# 12VPart.net
KiCad netlist of a schematic drawn in EAGLE
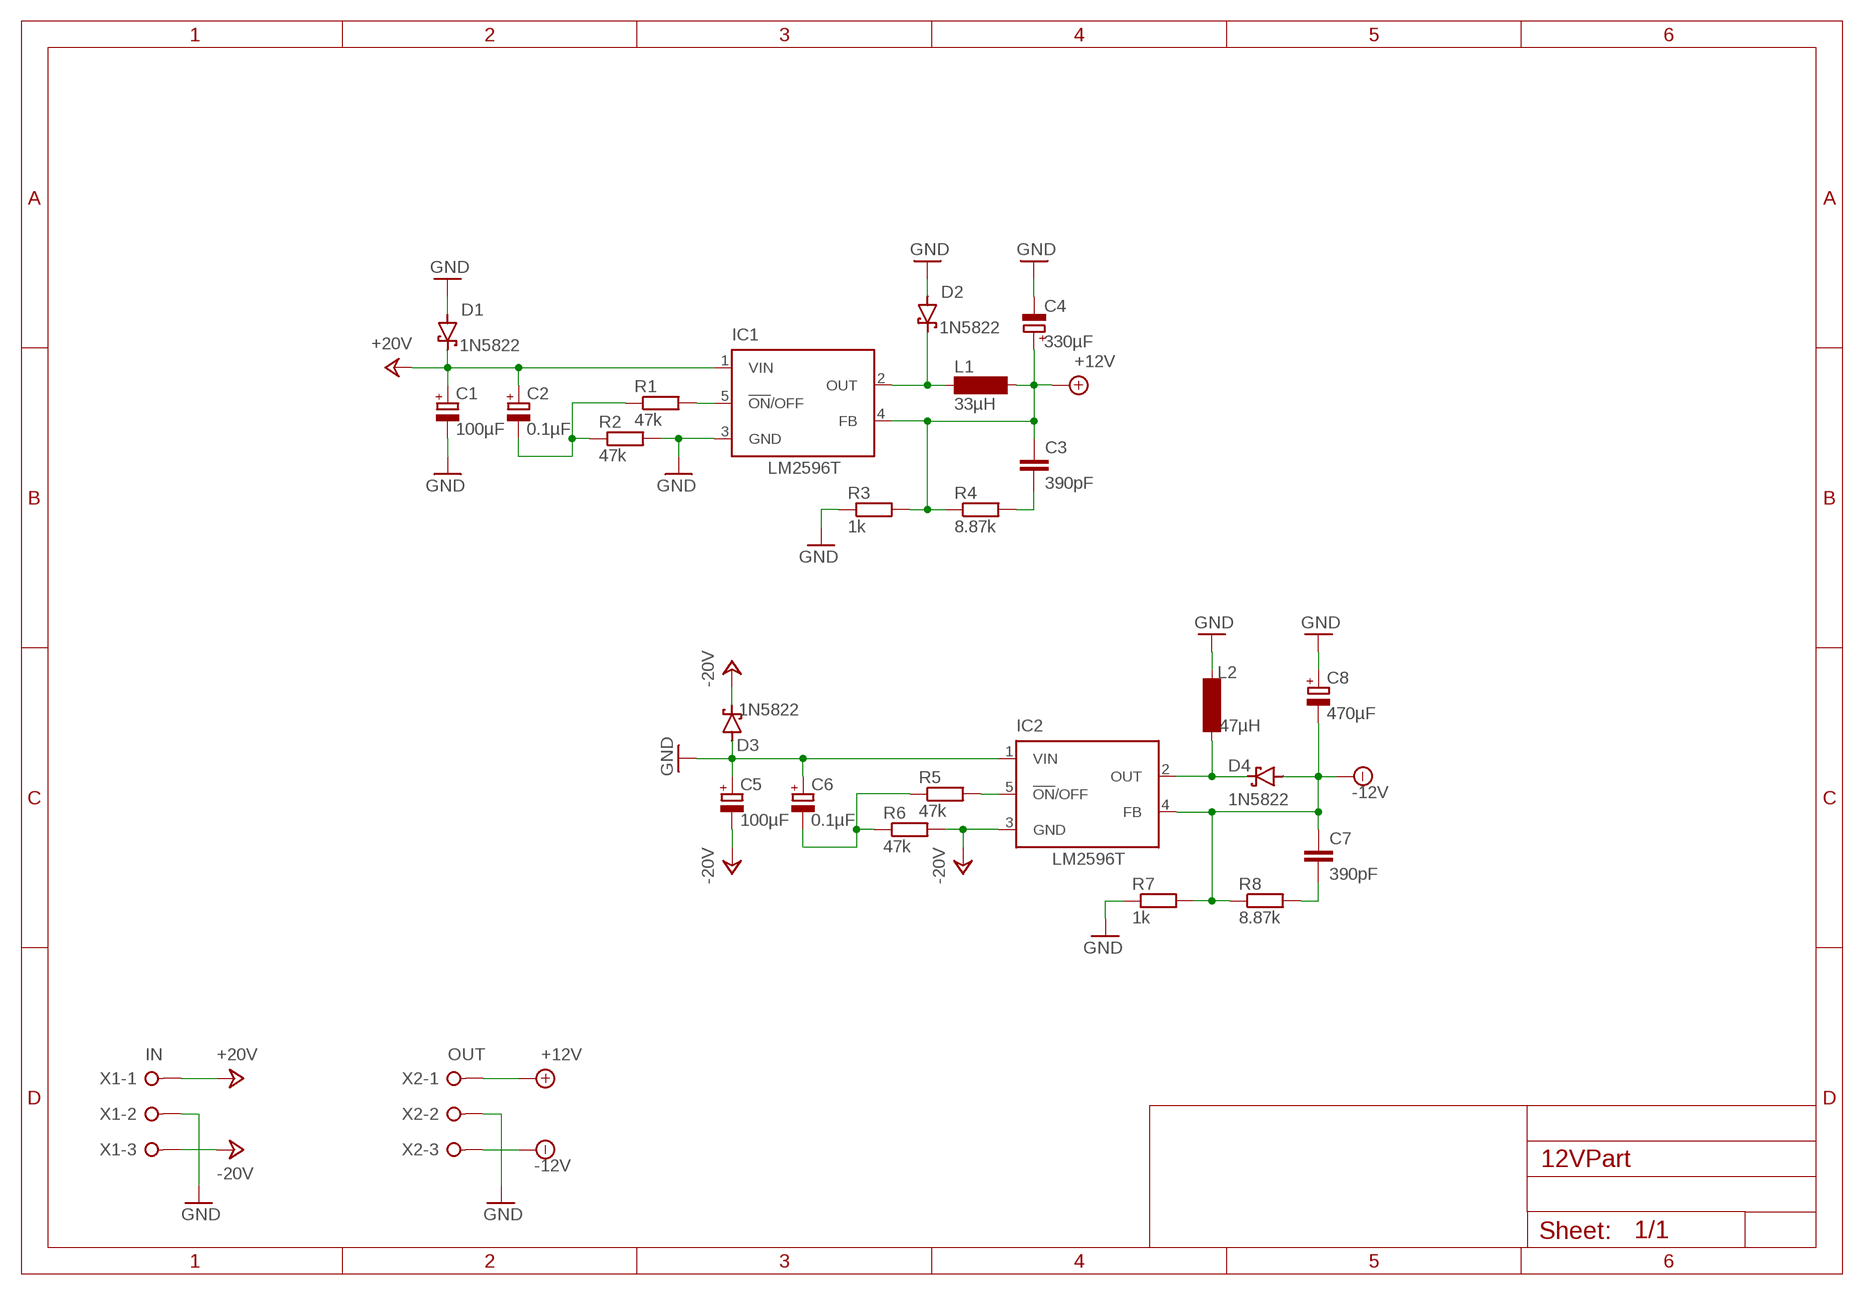
[diagram p0: schematic, sheet 1]

(export (version "E")
  (design (tool "Eeschema 10.0.6"))
  (components
    (comp (ref "C1")
      (value "100µF")
      (footprint "eagle-import:E2,5-6")
      (libsource (lib "eagle-import") (part "CPOL-EUE2.5-6"))
    )
    (comp (ref "C2")
      (value "0.1µF")
      (footprint "eagle-import:E1,8-4")
      (libsource (lib "eagle-import") (part "CPOL-EUE1.8-4"))
    )
    (comp (ref "C3")
      (value "390pF")
      (footprint "eagle-import:C050-024X044")
      (libsource (lib "eagle-import") (part "C-EU050-024X044"))
    )
    (comp (ref "C4")
      (value "330µF")
      (footprint "eagle-import:E3,5-8")
      (libsource (lib "eagle-import") (part "CPOL-EUE3.5-8"))
    )
    (comp (ref "C5")
      (value "100µF")
      (footprint "eagle-import:E2,5-6")
      (libsource (lib "eagle-import") (part "CPOL-EUE2.5-6"))
    )
    (comp (ref "C6")
      (value "0.1µF")
      (footprint "eagle-import:E1,8-4")
      (libsource (lib "eagle-import") (part "CPOL-EUE1.8-4"))
    )
    (comp (ref "C7")
      (value "390pF")
      (footprint "eagle-import:C050-024X044")
      (libsource (lib "eagle-import") (part "C-EU050-024X044"))
    )
    (comp (ref "C8")
      (value "470µF")
      (footprint "eagle-import:E3,5-8")
      (libsource (lib "eagle-import") (part "CPOL-EUE3.5-8"))
    )
    (comp (ref "D1")
      (value "1N5822")
      (footprint "eagle-import:C4111-15")
      (libsource (lib "eagle-import") (part "SCHOTTKY-DIODEC4111-15"))
    )
    (comp (ref "D2")
      (value "1N5822")
      (footprint "eagle-import:C4111-15")
      (libsource (lib "eagle-import") (part "SCHOTTKY-DIODEC4111-15"))
    )
    (comp (ref "D3")
      (value "1N5822")
      (footprint "eagle-import:C4111-15")
      (libsource (lib "eagle-import") (part "SCHOTTKY-DIODEC4111-15"))
    )
    (comp (ref "D4")
      (value "1N5822")
      (footprint "eagle-import:C4111-15")
      (libsource (lib "eagle-import") (part "SCHOTTKY-DIODEC4111-15"))
    )
    (comp (ref "IC1")
      (value "LM2596T")
      (footprint "eagle-import:T05D")
      (fields (field (name "MPN") "LM2596T-ADJ/LF02"))
      (libsource (lib "eagle-import") (part "LM2596T"))
    )
    (comp (ref "IC2")
      (value "LM2596T")
      (footprint "eagle-import:T05D")
      (fields (field (name "MPN") "LM2596T-ADJ/LF02"))
      (libsource (lib "eagle-import") (part "LM2596T"))
    )
    (comp (ref "L1")
      (value "33µH")
      (footprint "eagle-import:SD12-680")
      (fields (field (name "MF") "BUSSMANN") (field (name "MPN") "SD12-680"))
      (libsource (lib "eagle-import") (part "SD12-680"))
    )
    (comp (ref "L2")
      (value "47µH")
      (footprint "eagle-import:SD12-680")
      (fields (field (name "MF") "BUSSMANN") (field (name "MPN") "SD12-680"))
      (libsource (lib "eagle-import") (part "SD12-680"))
    )
    (comp (ref "R1")
      (value "47k")
      (footprint "eagle-import:0207_10")
      (libsource (lib "eagle-import") (part "R-EU_0207/10"))
    )
    (comp (ref "R2")
      (value "47k")
      (footprint "eagle-import:0207_10")
      (libsource (lib "eagle-import") (part "R-EU_0207/10"))
    )
    (comp (ref "R3")
      (value "1k")
      (footprint "eagle-import:0207_10")
      (libsource (lib "eagle-import") (part "R-EU_0207/10"))
    )
    (comp (ref "R4")
      (value "8.87k")
      (footprint "eagle-import:0207_10")
      (libsource (lib "eagle-import") (part "R-EU_0207/10"))
    )
    (comp (ref "R5")
      (value "47k")
      (footprint "eagle-import:0207_10")
      (libsource (lib "eagle-import") (part "R-EU_0207/10"))
    )
    (comp (ref "R6")
      (value "47k")
      (footprint "eagle-import:0207_10")
      (libsource (lib "eagle-import") (part "R-EU_0207/10"))
    )
    (comp (ref "R7")
      (value "1k")
      (footprint "eagle-import:0207_10")
      (libsource (lib "eagle-import") (part "R-EU_0207/10"))
    )
    (comp (ref "R8")
      (value "8.87k")
      (footprint "eagle-import:0207_10")
      (libsource (lib "eagle-import") (part "R-EU_0207/10"))
    )
    (comp (ref "X1")
      (value "IN")
      (footprint "eagle-import:W237-133")
      (libsource (lib "eagle-import") (part "W237-03P"))
    )
    (comp (ref "X2")
      (value "OUT")
      (footprint "eagle-import:W237-133")
      (libsource (lib "eagle-import") (part "W237-03P"))
    )
  )
  (nets
    (net (code "1") (name "+12V") (class "Default")
      (node (ref "C3") (pin "1") (pinfunction "1_1") (pintype "passive"))
      (node (ref "C4") (pin "+") (pinfunction "+_+") (pintype "passive"))
      (node (ref "IC1") (pin "4") (pinfunction "FB_4") (pintype "input"))
      (node (ref "L1") (pin "2") (pinfunction "2_2") (pintype "passive"))
      (node (ref "R3") (pin "2") (pinfunction "2_2") (pintype "passive"))
      (node (ref "R4") (pin "1") (pinfunction "1_1") (pintype "passive"))
      (node (ref "X2") (pin "1") (pinfunction "KL_1") (pintype "passive"))
    )
    (net (code "2") (name "+20V") (class "Default")
      (node (ref "C1") (pin "+") (pinfunction "+_+") (pintype "passive"))
      (node (ref "C2") (pin "+") (pinfunction "+_+") (pintype "passive"))
      (node (ref "D1") (pin "C") (pinfunction "C_C") (pintype "passive"))
      (node (ref "IC1") (pin "1") (pinfunction "VIN_1") (pintype "input"))
      (node (ref "X1") (pin "1") (pinfunction "KL_1") (pintype "passive"))
    )
    (net (code "3") (name "-12V") (class "Default")
      (node (ref "C7") (pin "1") (pinfunction "1_1") (pintype "passive"))
      (node (ref "C8") (pin "-") (pinfunction "-_-") (pintype "passive"))
      (node (ref "D4") (pin "A") (pinfunction "A_A") (pintype "passive"))
      (node (ref "IC2") (pin "4") (pinfunction "FB_4") (pintype "input"))
      (node (ref "R7") (pin "2") (pinfunction "2_2") (pintype "passive"))
      (node (ref "R8") (pin "1") (pinfunction "1_1") (pintype "passive"))
      (node (ref "X2") (pin "3") (pinfunction "KL_3") (pintype "passive"))
    )
    (net (code "4") (name "-20V") (class "Default")
      (node (ref "C5") (pin "-") (pinfunction "-_-") (pintype "passive"))
      (node (ref "D3") (pin "C") (pinfunction "C_C") (pintype "passive"))
      (node (ref "IC2") (pin "3") (pinfunction "GND_3") (pintype "power_in"))
      (node (ref "R6") (pin "2") (pinfunction "2_2") (pintype "passive"))
      (node (ref "X1") (pin "3") (pinfunction "KL_3") (pintype "passive"))
    )
    (net (code "5") (name "GND") (class "Default")
      (node (ref "C1") (pin "-") (pinfunction "-_-") (pintype "passive"))
      (node (ref "C4") (pin "-") (pinfunction "-_-") (pintype "passive"))
      (node (ref "C5") (pin "+") (pinfunction "+_+") (pintype "passive"))
      (node (ref "C6") (pin "+") (pinfunction "+_+") (pintype "passive"))
      (node (ref "C8") (pin "+") (pinfunction "+_+") (pintype "passive"))
      (node (ref "D1") (pin "A") (pinfunction "A_A") (pintype "passive"))
      (node (ref "D2") (pin "A") (pinfunction "A_A") (pintype "passive"))
      (node (ref "D3") (pin "A") (pinfunction "A_A") (pintype "passive"))
      (node (ref "IC1") (pin "3") (pinfunction "GND_3") (pintype "power_in"))
      (node (ref "IC2") (pin "1") (pinfunction "VIN_1") (pintype "input"))
      (node (ref "L2") (pin "2") (pinfunction "2_2") (pintype "passive"))
      (node (ref "R2") (pin "2") (pinfunction "2_2") (pintype "passive"))
      (node (ref "R3") (pin "1") (pinfunction "1_1") (pintype "passive"))
      (node (ref "R7") (pin "1") (pinfunction "1_1") (pintype "passive"))
      (node (ref "X1") (pin "2") (pinfunction "KL_2") (pintype "passive"))
      (node (ref "X2") (pin "2") (pinfunction "KL_2") (pintype "passive"))
    )
    (net (code "6") (name "Net-(C2-Pad-)") (class "Default")
      (node (ref "C2") (pin "-") (pinfunction "-_-") (pintype "passive"))
      (node (ref "R1") (pin "1") (pinfunction "1_1") (pintype "passive"))
      (node (ref "R2") (pin "1") (pinfunction "1_1") (pintype "passive"))
    )
    (net (code "7") (name "Net-(C3-Pad2)") (class "Default")
      (node (ref "C3") (pin "2") (pinfunction "2_2") (pintype "passive"))
      (node (ref "R4") (pin "2") (pinfunction "2_2") (pintype "passive"))
    )
    (net (code "8") (name "Net-(C6-Pad-)") (class "Default")
      (node (ref "C6") (pin "-") (pinfunction "-_-") (pintype "passive"))
      (node (ref "R5") (pin "1") (pinfunction "1_1") (pintype "passive"))
      (node (ref "R6") (pin "1") (pinfunction "1_1") (pintype "passive"))
    )
    (net (code "9") (name "Net-(C7-Pad2)") (class "Default")
      (node (ref "C7") (pin "2") (pinfunction "2_2") (pintype "passive"))
      (node (ref "R8") (pin "2") (pinfunction "2_2") (pintype "passive"))
    )
    (net (code "10") (name "Net-(IC1-OUT)") (class "Default")
      (node (ref "D2") (pin "C") (pinfunction "C_C") (pintype "passive"))
      (node (ref "IC1") (pin "2") (pinfunction "OUT_2") (pintype "output"))
      (node (ref "L1") (pin "1") (pinfunction "1_1") (pintype "passive"))
    )
    (net (code "11") (name "Net-(IC1-~{ON}{slash}OFF)") (class "Default")
      (node (ref "IC1") (pin "5") (pinfunction "~{ON}/OFF_5") (pintype "input"))
      (node (ref "R1") (pin "2") (pinfunction "2_2") (pintype "passive"))
    )
    (net (code "12") (name "Net-(IC2-OUT)") (class "Default")
      (node (ref "D4") (pin "C") (pinfunction "C_C") (pintype "passive"))
      (node (ref "IC2") (pin "2") (pinfunction "OUT_2") (pintype "output"))
      (node (ref "L2") (pin "1") (pinfunction "1_1") (pintype "passive"))
    )
    (net (code "13") (name "Net-(IC2-~{ON}{slash}OFF)") (class "Default")
      (node (ref "IC2") (pin "5") (pinfunction "~{ON}/OFF_5") (pintype "input"))
      (node (ref "R5") (pin "2") (pinfunction "2_2") (pintype "passive"))
    )
  )
)
